# Main.net
KiCad netlist of a schematic drawn in Altium Designer
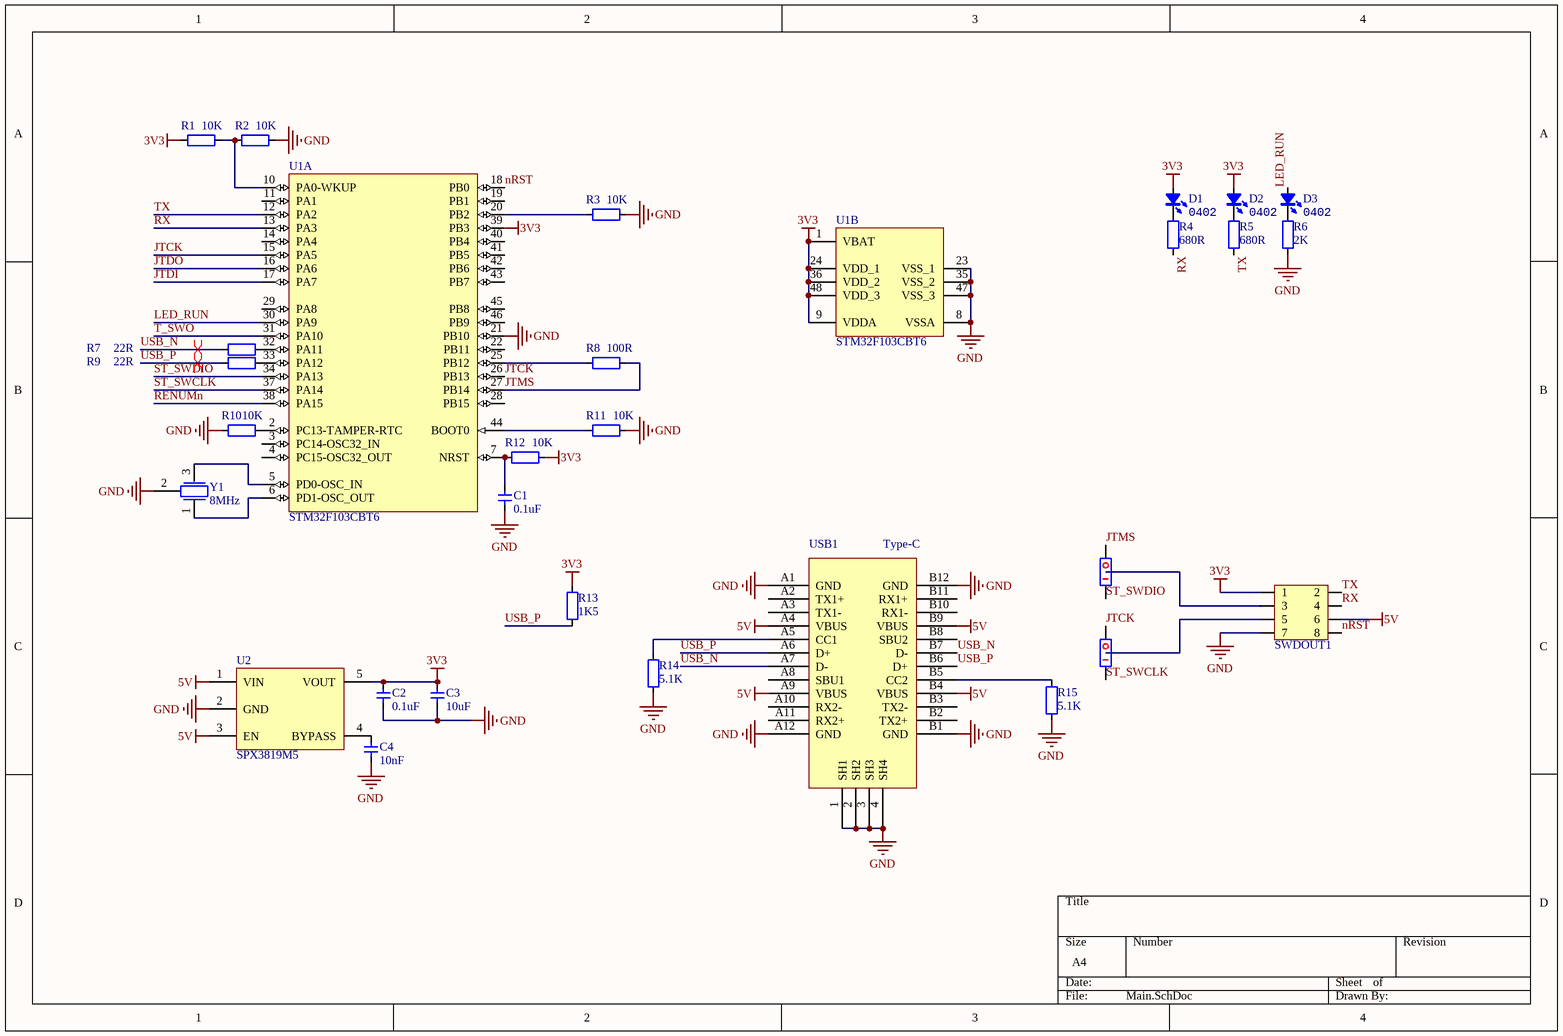
[diagram p0: Main.SchDoc]

(export (version "E")
  (design (tool "Eeschema 10.0.6"))
  (components
    (comp (ref "C1")
      (value "0.1uF")
      (footprint "CAP_0402")
      (description "Capacitor")
      (libsource (lib "MyPcbLib") (part "电容-0402"))
    )
    (comp (ref "C2")
      (value "0.1uF")
      (footprint "CAP_0402")
      (description "Capacitor")
      (libsource (lib "MyPcbLib") (part "电容-0402"))
    )
    (comp (ref "C3")
      (value "10uF")
      (footprint "CAP_0402")
      (description "Capacitor")
      (libsource (lib "MyPcbLib") (part "电容-0402"))
    )
    (comp (ref "C4")
      (value "10nF")
      (footprint "CAP_0402")
      (description "Capacitor")
      (libsource (lib "MyPcbLib") (part "电容-0402"))
    )
    (comp (ref "D1")
      (value "color?")
      (footprint "LED_0402_BLUE")
      (description "LED")
      (fields (field (name "TYPE") "0402"))
      (libsource (lib "KitSprout") (part "LED_0402"))
    )
    (comp (ref "D2")
      (value "color?")
      (footprint "LED_0402_YELLOW")
      (description "LED")
      (fields (field (name "TYPE") "0402"))
      (libsource (lib "KitSprout") (part "LED_0402"))
    )
    (comp (ref "D3")
      (value "color?")
      (footprint "LED_0402_GREEN")
      (description "LED")
      (fields (field (name "TYPE") "0402"))
      (libsource (lib "KitSprout") (part "LED_0402"))
    )
    (comp (ref "J1")
      (value "选择跳线")
      (footprint "jumper-3")
      (description "Resistor")
      (fields (field (name "PUBLISHER") "Altium Limited"))
      (libsource (lib "MyPcbLib") (part "选择跳线"))
    )
    (comp (ref "J2")
      (value "选择跳线")
      (footprint "jumper-3")
      (description "Resistor")
      (fields (field (name "PUBLISHER") "Altium Limited"))
      (libsource (lib "MyPcbLib") (part "选择跳线"))
    )
    (comp (ref "R1")
      (value "10K")
      (footprint "RES_0402")
      (description "Resistor")
      (libsource (lib "MyPcbLib") (part "电阻-0402"))
    )
    (comp (ref "R2")
      (value "10K")
      (footprint "RES_0402")
      (description "Resistor")
      (libsource (lib "MyPcbLib") (part "电阻-0402"))
    )
    (comp (ref "R3")
      (value "10K")
      (footprint "RES_0402")
      (description "Resistor")
      (libsource (lib "MyPcbLib") (part "电阻-0402"))
    )
    (comp (ref "R4")
      (value "680R")
      (footprint "RES_0402")
      (description "Resistor")
      (libsource (lib "") (part "电阻-0402_1"))
    )
    (comp (ref "R5")
      (value "680R")
      (footprint "RES_0402")
      (description "Resistor")
      (libsource (lib "") (part "电阻-0402_1"))
    )
    (comp (ref "R6")
      (value "2K")
      (footprint "RES_0402")
      (description "Resistor")
      (libsource (lib "") (part "电阻-0402_1"))
    )
    (comp (ref "R7")
      (value "22R")
      (footprint "RES_0402")
      (description "Resistor")
      (libsource (lib "MyPcbLib") (part "电阻-0402"))
    )
    (comp (ref "R8")
      (value "100R")
      (footprint "RES_0402")
      (description "Resistor")
      (libsource (lib "MyPcbLib") (part "电阻-0402"))
    )
    (comp (ref "R9")
      (value "22R")
      (footprint "RES_0402")
      (description "Resistor")
      (libsource (lib "MyPcbLib") (part "电阻-0402"))
    )
    (comp (ref "R10")
      (value "10K")
      (footprint "RES_0402")
      (description "Resistor")
      (libsource (lib "MyPcbLib") (part "电阻-0402"))
    )
    (comp (ref "R11")
      (value "10K")
      (footprint "RES_0402")
      (description "Resistor")
      (libsource (lib "MyPcbLib") (part "电阻-0402"))
    )
    (comp (ref "R12")
      (value "10K")
      (footprint "RES_0402")
      (description "Resistor")
      (libsource (lib "MyPcbLib") (part "电阻-0402"))
    )
    (comp (ref "R13")
      (value "1K5")
      (footprint "RES_0402")
      (description "Resistor")
      (libsource (lib "") (part "电阻-0402_1"))
    )
    (comp (ref "R14")
      (value "5.1K")
      (footprint "RES_0402")
      (description "Resistor")
      (libsource (lib "") (part "电阻-0402_2"))
    )
    (comp (ref "R15")
      (value "5.1K")
      (footprint "RES_0402")
      (description "Resistor")
      (libsource (lib "") (part "电阻-0402_2"))
    )
    (comp (ref "SWDOUT1")
      (value "HDR2x4_2.54")
      (footprint "HDR2X4_2.54_180H")
      (description "Header")
      (libsource (lib "MyPcbLib") (part "HDR2x4_2.54"))
    )
    (comp (ref "U1")
      (value "STM32F103CBT6")
      (footprint "LQFP-48")
      (libsource (lib "STMicroelectronics STM32 F1") (part "STM32F103CBT6"))
    )
    (comp (ref "U2")
      (value "SPX3819M5")
      (footprint "SOT23-5")
      (description "LDO")
      (libsource (lib "MyPcbLib") (part "SPX3819M5"))
    )
    (comp (ref "USB1")
      (value "Type-C")
      (footprint "Type-C-TOP")
      (libsource (lib "MyPcbLib") (part "USB-Type-C-TOP"))
    )
    (comp (ref "Y1")
      (value "8MHz")
      (footprint "晶振-3P")
      (description "村田贴片")
      (libsource (lib "MyPcbLib") (part "晶振-3Pin"))
    )
  )
  (nets
    (net (code "1") (name "/JTCK") (class "Default")
      (node (ref "J2") (pin "1") (pinfunction "1_1") (pintype "passive"))
      (node (ref "U1") (pin "15") (pinfunction "PA5_15") (pintype "bidirectional"))
      (node (ref "U1") (pin "26") (pinfunction "PB13_26") (pintype "bidirectional"))
    )
    (net (code "2") (name "/JTDI") (class "Default")
      (node (ref "U1") (pin "17") (pinfunction "PA7_17") (pintype "bidirectional"))
    )
    (net (code "3") (name "/JTDO") (class "Default")
      (node (ref "U1") (pin "16") (pinfunction "PA6_16") (pintype "bidirectional"))
    )
    (net (code "4") (name "/JTMS") (class "Default")
      (node (ref "J1") (pin "1") (pinfunction "1_1") (pintype "passive"))
      (node (ref "R8") (pin "2") (pinfunction "2_2") (pintype "passive"))
      (node (ref "U1") (pin "27") (pinfunction "PB14_27") (pintype "bidirectional"))
    )
    (net (code "5") (name "/LED_RUN") (class "Default")
      (node (ref "D3") (pin "1") (pinfunction "A_1") (pintype "passive"))
      (node (ref "U1") (pin "30") (pinfunction "PA9_30") (pintype "bidirectional"))
    )
    (net (code "6") (name "/RENUMn") (class "Default")
      (node (ref "U1") (pin "38") (pinfunction "PA15_38") (pintype "bidirectional"))
    )
    (net (code "7") (name "/RX") (class "Default")
      (node (ref "R4") (pin "1") (pinfunction "1_1") (pintype "passive"))
      (node (ref "SWDOUT1") (pin "4") (pinfunction "4_4") (pintype "passive"))
      (node (ref "U1") (pin "13") (pinfunction "PA3_13") (pintype "bidirectional"))
    )
    (net (code "8") (name "/ST_SWCLK") (class "Default")
      (node (ref "J2") (pin "3") (pinfunction "3_3") (pintype "passive"))
      (node (ref "U1") (pin "37") (pinfunction "PA14_37") (pintype "bidirectional"))
    )
    (net (code "9") (name "/ST_SWDIO") (class "Default")
      (node (ref "J1") (pin "3") (pinfunction "3_3") (pintype "passive"))
      (node (ref "U1") (pin "34") (pinfunction "PA13_34") (pintype "bidirectional"))
    )
    (net (code "10") (name "/TX") (class "Default")
      (node (ref "R5") (pin "1") (pinfunction "1_1") (pintype "passive"))
      (node (ref "SWDOUT1") (pin "2") (pinfunction "2_2") (pintype "passive"))
      (node (ref "U1") (pin "12") (pinfunction "PA2_12") (pintype "bidirectional"))
    )
    (net (code "11") (name "/T_SWO") (class "Default")
      (node (ref "U1") (pin "31") (pinfunction "PA10_31") (pintype "bidirectional"))
    )
    (net (code "12") (name "/USB_N") (class "Default")
      (node (ref "R7") (pin "1") (pinfunction "1_1") (pintype "passive"))
      (node (ref "USB1") (pin "A7") (pinfunction "D-_A7") (pintype "passive"))
      (node (ref "USB1") (pin "B7") (pinfunction "D-_B7") (pintype "passive"))
    )
    (net (code "13") (name "/USB_P") (class "Default")
      (node (ref "R13") (pin "1") (pinfunction "1_1") (pintype "passive"))
      (node (ref "R9") (pin "1") (pinfunction "1_1") (pintype "passive"))
      (node (ref "USB1") (pin "A6") (pinfunction "D+_A6") (pintype "passive"))
      (node (ref "USB1") (pin "B6") (pinfunction "D+_B6") (pintype "passive"))
    )
    (net (code "14") (name "/nRST") (class "Default")
      (node (ref "SWDOUT1") (pin "8") (pinfunction "8_8") (pintype "passive"))
      (node (ref "U1") (pin "18") (pinfunction "PB0_18") (pintype "bidirectional"))
    )
    (net (code "15") (name "3V3") (class "Default")
      (node (ref "C2") (pin "2") (pinfunction "2_2") (pintype "passive"))
      (node (ref "C3") (pin "2") (pinfunction "2_2") (pintype "passive"))
      (node (ref "D1") (pin "1") (pinfunction "A_1") (pintype "passive"))
      (node (ref "D2") (pin "1") (pinfunction "A_1") (pintype "passive"))
      (node (ref "R1") (pin "1") (pinfunction "1_1") (pintype "passive"))
      (node (ref "R12") (pin "2") (pinfunction "2_2") (pintype "passive"))
      (node (ref "R13") (pin "2") (pinfunction "2_2") (pintype "passive"))
      (node (ref "SWDOUT1") (pin "1") (pinfunction "1_1") (pintype "passive"))
      (node (ref "U1") (pin "1") (pinfunction "VBAT_1") (pintype "power_in"))
      (node (ref "U1") (pin "24") (pinfunction "VDD_1_24") (pintype "power_in"))
      (node (ref "U1") (pin "36") (pinfunction "VDD_2_36") (pintype "power_in"))
      (node (ref "U1") (pin "39") (pinfunction "PB3_39") (pintype "bidirectional"))
      (node (ref "U1") (pin "48") (pinfunction "VDD_3_48") (pintype "power_in"))
      (node (ref "U1") (pin "9") (pinfunction "VDDA_9") (pintype "power_in"))
      (node (ref "U2") (pin "5") (pinfunction "VOUT_5") (pintype "passive"))
    )
    (net (code "16") (name "5V") (class "Default")
      (node (ref "SWDOUT1") (pin "6") (pinfunction "6_6") (pintype "passive"))
      (node (ref "U2") (pin "1") (pinfunction "VIN_1") (pintype "passive"))
      (node (ref "U2") (pin "3") (pinfunction "EN_3") (pintype "passive"))
      (node (ref "USB1") (pin "A4") (pinfunction "VBUS_A4") (pintype "passive"))
      (node (ref "USB1") (pin "A9") (pinfunction "VBUS_A9") (pintype "passive"))
      (node (ref "USB1") (pin "B4") (pinfunction "VBUS_B4") (pintype "passive"))
      (node (ref "USB1") (pin "B9") (pinfunction "VBUS_B9") (pintype "passive"))
    )
    (net (code "17") (name "GND") (class "Default")
      (node (ref "C1") (pin "1") (pinfunction "1_1") (pintype "passive"))
      (node (ref "C2") (pin "1") (pinfunction "1_1") (pintype "passive"))
      (node (ref "C3") (pin "1") (pinfunction "1_1") (pintype "passive"))
      (node (ref "C4") (pin "1") (pinfunction "1_1") (pintype "passive"))
      (node (ref "R10") (pin "1") (pinfunction "1_1") (pintype "passive"))
      (node (ref "R11") (pin "2") (pinfunction "2_2") (pintype "passive"))
      (node (ref "R14") (pin "2") (pinfunction "2_2") (pintype "passive"))
      (node (ref "R15") (pin "2") (pinfunction "2_2") (pintype "passive"))
      (node (ref "R2") (pin "2") (pinfunction "2_2") (pintype "passive"))
      (node (ref "R3") (pin "2") (pinfunction "2_2") (pintype "passive"))
      (node (ref "R6") (pin "1") (pinfunction "1_1") (pintype "passive"))
      (node (ref "SWDOUT1") (pin "7") (pinfunction "7_7") (pintype "passive"))
      (node (ref "U1") (pin "21") (pinfunction "PB10_21") (pintype "bidirectional"))
      (node (ref "U1") (pin "23") (pinfunction "VSS_1_23") (pintype "power_in"))
      (node (ref "U1") (pin "35") (pinfunction "VSS_2_35") (pintype "power_in"))
      (node (ref "U1") (pin "47") (pinfunction "VSS_3_47") (pintype "power_in"))
      (node (ref "U1") (pin "8") (pinfunction "VSSA_8") (pintype "power_in"))
      (node (ref "U2") (pin "2") (pinfunction "GND_2") (pintype "passive"))
      (node (ref "USB1") (pin "1") (pinfunction "SH1_1") (pintype "passive"))
      (node (ref "USB1") (pin "2") (pinfunction "SH2_2") (pintype "passive"))
      (node (ref "USB1") (pin "3") (pinfunction "SH3_3") (pintype "passive"))
      (node (ref "USB1") (pin "4") (pinfunction "SH4_4") (pintype "passive"))
      (node (ref "USB1") (pin "A1") (pinfunction "GND_A1") (pintype "passive"))
      (node (ref "USB1") (pin "A12") (pinfunction "GND_A12") (pintype "passive"))
      (node (ref "USB1") (pin "B1") (pinfunction "GND_B1") (pintype "passive"))
      (node (ref "USB1") (pin "B12") (pinfunction "GND_B12") (pintype "passive"))
      (node (ref "Y1") (pin "2") (pinfunction "2_2") (pintype "passive"))
    )
    (net (code "18") (name "Net-(D1-K)") (class "Default")
      (node (ref "D1") (pin "2") (pinfunction "K_2") (pintype "passive"))
      (node (ref "R4") (pin "2") (pinfunction "2_2") (pintype "passive"))
    )
    (net (code "19") (name "Net-(D2-K)") (class "Default")
      (node (ref "D2") (pin "2") (pinfunction "K_2") (pintype "passive"))
      (node (ref "R5") (pin "2") (pinfunction "2_2") (pintype "passive"))
    )
    (net (code "20") (name "Net-(D3-K)") (class "Default")
      (node (ref "D3") (pin "2") (pinfunction "K_2") (pintype "passive"))
      (node (ref "R6") (pin "2") (pinfunction "2_2") (pintype "passive"))
    )
    (net (code "21") (name "Net-(J1-Pad2)") (class "Default")
      (node (ref "J1") (pin "2") (pinfunction "2_2") (pintype "passive"))
      (node (ref "SWDOUT1") (pin "3") (pinfunction "3_3") (pintype "passive"))
    )
    (net (code "22") (name "Net-(J2-Pad2)") (class "Default")
      (node (ref "J2") (pin "2") (pinfunction "2_2") (pintype "passive"))
      (node (ref "SWDOUT1") (pin "5") (pinfunction "5_5") (pintype "passive"))
    )
    (net (code "23") (name "Net-(U1A-BOOT0)") (class "Default")
      (node (ref "R11") (pin "1") (pinfunction "1_1") (pintype "passive"))
      (node (ref "U1") (pin "44") (pinfunction "BOOT0_44") (pintype "input"))
    )
    (net (code "24") (name "Net-(U1A-NRST)") (class "Default")
      (node (ref "C1") (pin "2") (pinfunction "2_2") (pintype "passive"))
      (node (ref "R12") (pin "1") (pinfunction "1_1") (pintype "passive"))
      (node (ref "U1") (pin "7") (pinfunction "NRST_7") (pintype "bidirectional"))
    )
    (net (code "25") (name "Net-(U1A-PA0-WKUP)") (class "Default")
      (node (ref "R1") (pin "2") (pinfunction "2_2") (pintype "passive"))
      (node (ref "R2") (pin "1") (pinfunction "1_1") (pintype "passive"))
      (node (ref "U1") (pin "10") (pinfunction "PA0-WKUP_10") (pintype "bidirectional"))
    )
    (net (code "26") (name "Net-(U1A-PA11)") (class "Default")
      (node (ref "R7") (pin "2") (pinfunction "2_2") (pintype "passive"))
      (node (ref "U1") (pin "32") (pinfunction "PA11_32") (pintype "bidirectional"))
    )
    (net (code "27") (name "Net-(U1A-PA12)") (class "Default")
      (node (ref "R9") (pin "2") (pinfunction "2_2") (pintype "passive"))
      (node (ref "U1") (pin "33") (pinfunction "PA12_33") (pintype "bidirectional"))
    )
    (net (code "28") (name "Net-(U1A-PB2)") (class "Default")
      (node (ref "R3") (pin "1") (pinfunction "1_1") (pintype "passive"))
      (node (ref "U1") (pin "20") (pinfunction "PB2_20") (pintype "bidirectional"))
    )
    (net (code "29") (name "Net-(U1A-PB12)") (class "Default")
      (node (ref "R8") (pin "1") (pinfunction "1_1") (pintype "passive"))
      (node (ref "U1") (pin "25") (pinfunction "PB12_25") (pintype "bidirectional"))
    )
    (net (code "30") (name "Net-(U1A-PC13-TAMPER-RTC)") (class "Default")
      (node (ref "R10") (pin "2") (pinfunction "2_2") (pintype "passive"))
      (node (ref "U1") (pin "2") (pinfunction "PC13-TAMPER-RTC_2") (pintype "bidirectional"))
    )
    (net (code "31") (name "Net-(U1A-PD0-OSC_IN)") (class "Default")
      (node (ref "U1") (pin "5") (pinfunction "PD0-OSC_IN_5") (pintype "bidirectional"))
      (node (ref "Y1") (pin "3") (pinfunction "3_3") (pintype "passive"))
    )
    (net (code "32") (name "Net-(U1A-PD1-OSC_OUT)") (class "Default")
      (node (ref "U1") (pin "6") (pinfunction "PD1-OSC_OUT_6") (pintype "bidirectional"))
      (node (ref "Y1") (pin "1") (pinfunction "1_1") (pintype "passive"))
    )
    (net (code "33") (name "Net-(U2-BYPASS)") (class "Default")
      (node (ref "C4") (pin "2") (pinfunction "2_2") (pintype "passive"))
      (node (ref "U2") (pin "4") (pinfunction "BYPASS_4") (pintype "passive"))
    )
    (net (code "34") (name "Net-(USB1-CC1)") (class "Default")
      (node (ref "R14") (pin "1") (pinfunction "1_1") (pintype "passive"))
      (node (ref "USB1") (pin "A5") (pinfunction "CC1_A5") (pintype "passive"))
    )
    (net (code "35") (name "Net-(USB1-CC2)") (class "Default")
      (node (ref "R15") (pin "1") (pinfunction "1_1") (pintype "passive"))
      (node (ref "USB1") (pin "B5") (pinfunction "CC2_B5") (pintype "passive"))
    )
    (net (code "36") (name "unconnected-(U1A-PA1-Pad11)") (class "Default")
      (node (ref "U1") (pin "11") (pinfunction "PA1_11") (pintype "bidirectional"))
    )
    (net (code "37") (name "unconnected-(U1A-PA4-Pad14)") (class "Default")
      (node (ref "U1") (pin "14") (pinfunction "PA4_14") (pintype "bidirectional"))
    )
    (net (code "38") (name "unconnected-(U1A-PA8-Pad29)") (class "Default")
      (node (ref "U1") (pin "29") (pinfunction "PA8_29") (pintype "bidirectional"))
    )
    (net (code "39") (name "unconnected-(U1A-PB1-Pad19)") (class "Default")
      (node (ref "U1") (pin "19") (pinfunction "PB1_19") (pintype "bidirectional"))
    )
    (net (code "40") (name "unconnected-(U1A-PB4-Pad40)") (class "Default")
      (node (ref "U1") (pin "40") (pinfunction "PB4_40") (pintype "bidirectional"))
    )
    (net (code "41") (name "unconnected-(U1A-PB5-Pad41)") (class "Default")
      (node (ref "U1") (pin "41") (pinfunction "PB5_41") (pintype "bidirectional"))
    )
    (net (code "42") (name "unconnected-(U1A-PB6-Pad42)") (class "Default")
      (node (ref "U1") (pin "42") (pinfunction "PB6_42") (pintype "bidirectional"))
    )
    (net (code "43") (name "unconnected-(U1A-PB7-Pad43)") (class "Default")
      (node (ref "U1") (pin "43") (pinfunction "PB7_43") (pintype "bidirectional"))
    )
    (net (code "44") (name "unconnected-(U1A-PB8-Pad45)") (class "Default")
      (node (ref "U1") (pin "45") (pinfunction "PB8_45") (pintype "bidirectional"))
    )
    (net (code "45") (name "unconnected-(U1A-PB9-Pad46)") (class "Default")
      (node (ref "U1") (pin "46") (pinfunction "PB9_46") (pintype "bidirectional"))
    )
    (net (code "46") (name "unconnected-(U1A-PB11-Pad22)") (class "Default")
      (node (ref "U1") (pin "22") (pinfunction "PB11_22") (pintype "bidirectional"))
    )
    (net (code "47") (name "unconnected-(U1A-PB15-Pad28)") (class "Default")
      (node (ref "U1") (pin "28") (pinfunction "PB15_28") (pintype "bidirectional"))
    )
    (net (code "48") (name "unconnected-(U1A-PC14-OSC32_IN-Pad3)") (class "Default")
      (node (ref "U1") (pin "3") (pinfunction "PC14-OSC32_IN_3") (pintype "bidirectional"))
    )
    (net (code "49") (name "unconnected-(U1A-PC15-OSC32_OUT-Pad4)") (class "Default")
      (node (ref "U1") (pin "4") (pinfunction "PC15-OSC32_OUT_4") (pintype "bidirectional"))
    )
    (net (code "50") (name "unconnected-(USB1-RX1+-PadB11)") (class "Default")
      (node (ref "USB1") (pin "B11") (pinfunction "RX1+_B11") (pintype "passive"))
    )
    (net (code "51") (name "unconnected-(USB1-RX1--PadB10)") (class "Default")
      (node (ref "USB1") (pin "B10") (pinfunction "RX1-_B10") (pintype "passive"))
    )
    (net (code "52") (name "unconnected-(USB1-RX2+-PadA11)") (class "Default")
      (node (ref "USB1") (pin "A11") (pinfunction "RX2+_A11") (pintype "passive"))
    )
    (net (code "53") (name "unconnected-(USB1-RX2--PadA10)") (class "Default")
      (node (ref "USB1") (pin "A10") (pinfunction "RX2-_A10") (pintype "passive"))
    )
    (net (code "54") (name "unconnected-(USB1-SBU1-PadA8)") (class "Default")
      (node (ref "USB1") (pin "A8") (pinfunction "SBU1_A8") (pintype "passive"))
    )
    (net (code "55") (name "unconnected-(USB1-SBU2-PadB8)") (class "Default")
      (node (ref "USB1") (pin "B8") (pinfunction "SBU2_B8") (pintype "passive"))
    )
    (net (code "56") (name "unconnected-(USB1-TX1+-PadA2)") (class "Default")
      (node (ref "USB1") (pin "A2") (pinfunction "TX1+_A2") (pintype "passive"))
    )
    (net (code "57") (name "unconnected-(USB1-TX1--PadA3)") (class "Default")
      (node (ref "USB1") (pin "A3") (pinfunction "TX1-_A3") (pintype "passive"))
    )
    (net (code "58") (name "unconnected-(USB1-TX2+-PadB2)") (class "Default")
      (node (ref "USB1") (pin "B2") (pinfunction "TX2+_B2") (pintype "passive"))
    )
    (net (code "59") (name "unconnected-(USB1-TX2--PadB3)") (class "Default")
      (node (ref "USB1") (pin "B3") (pinfunction "TX2-_B3") (pintype "passive"))
    )
  )
)
